# Actor_8_Channel.net
KiCad netlist of a schematic drawn in EAGLE
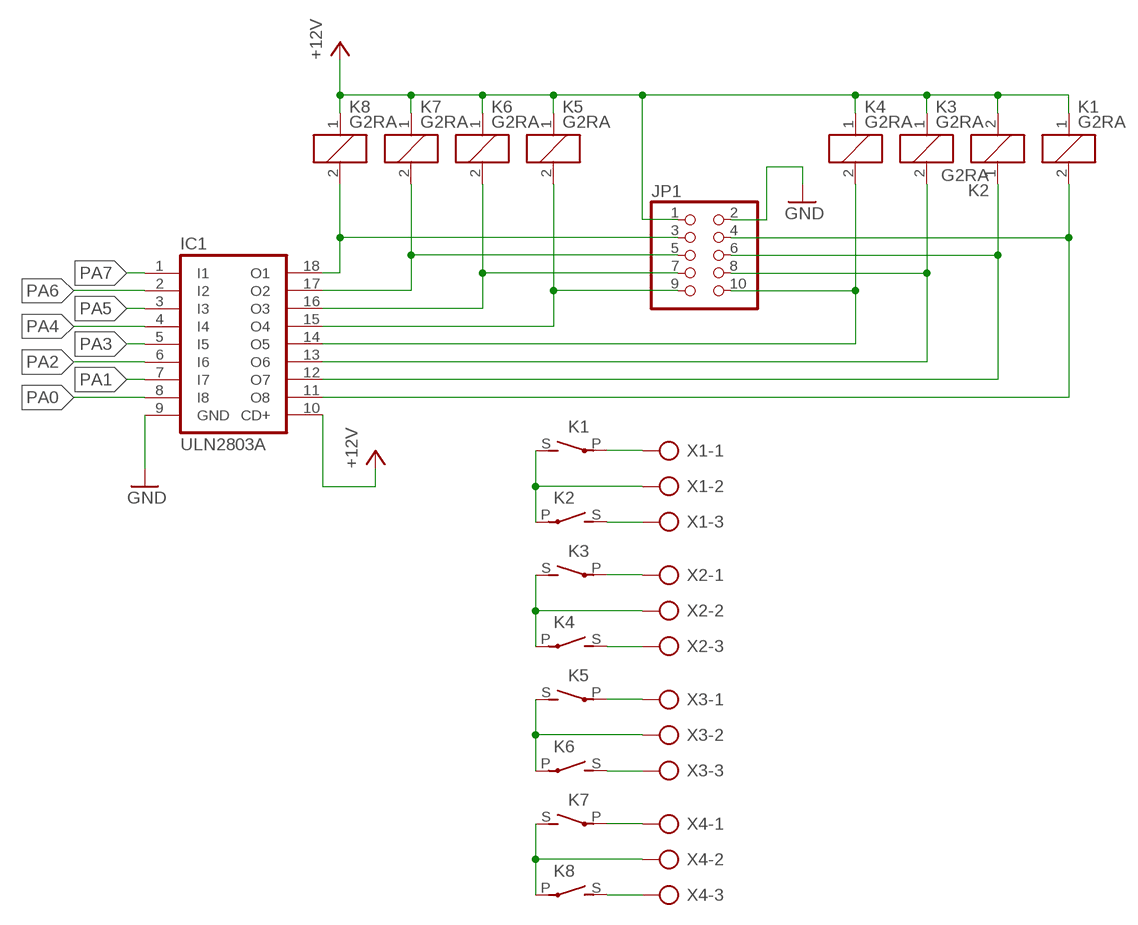
[diagram p0: schematic, sheet 1, part 1 of 2]
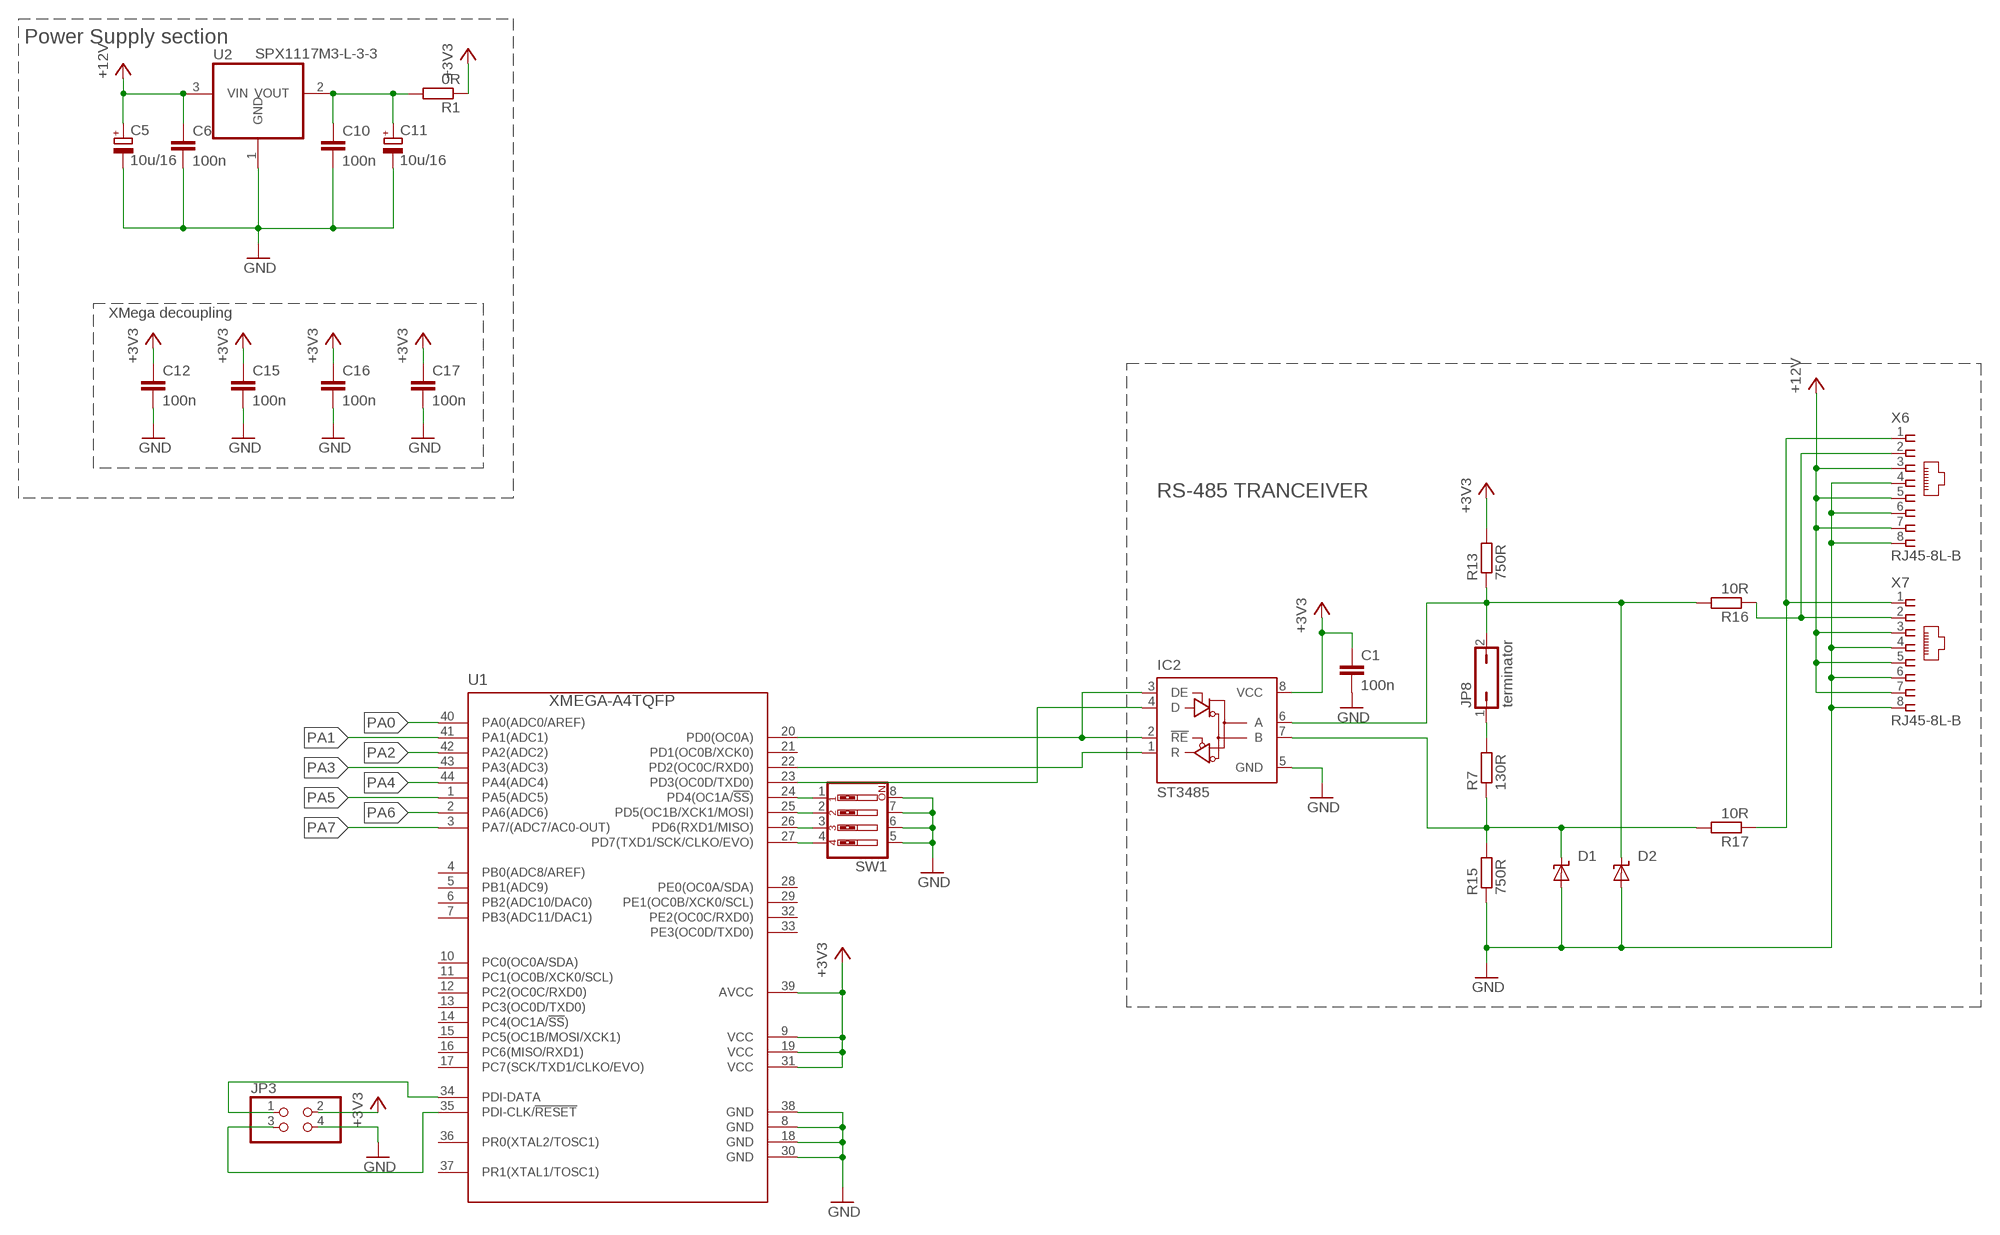
[diagram p1: schematic, sheet 1, part 2 of 2]

(export (version "E")
  (design (tool "Eeschema 10.0.6"))
  (components
    (comp (ref "C1")
      (value "100n")
      (footprint "eagle-import:C1206")
      (libsource (lib "eagle-import") (part "C-EUC1206"))
    )
    (comp (ref "C5")
      (value "10u/16")
      (footprint "eagle-import:SMC_C")
      (libsource (lib "eagle-import") (part "CPOL-EUSMCC"))
    )
    (comp (ref "C6")
      (value "100n")
      (footprint "eagle-import:C1206")
      (libsource (lib "eagle-import") (part "C-EUC1206"))
    )
    (comp (ref "C10")
      (value "100n")
      (footprint "eagle-import:C1206")
      (libsource (lib "eagle-import") (part "C-EUC1206"))
    )
    (comp (ref "C11")
      (value "10u/16")
      (footprint "eagle-import:SMC_C")
      (libsource (lib "eagle-import") (part "CPOL-EUSMCC"))
    )
    (comp (ref "C12")
      (value "100n")
      (footprint "eagle-import:C1206")
      (libsource (lib "eagle-import") (part "C-EUC1206"))
    )
    (comp (ref "C15")
      (value "100n")
      (footprint "eagle-import:C1206")
      (libsource (lib "eagle-import") (part "C-EUC1206"))
    )
    (comp (ref "C16")
      (value "100n")
      (footprint "eagle-import:C1206")
      (libsource (lib "eagle-import") (part "C-EUC1206"))
    )
    (comp (ref "C17")
      (value "100n")
      (footprint "eagle-import:C1206")
      (libsource (lib "eagle-import") (part "C-EUC1206"))
    )
    (comp (ref "D1")
      (value "SUPPRESSOR-SMBJ")
      (footprint "eagle-import:SMBJ")
      (libsource (lib "eagle-import") (part "SUPPRESSOR-SMBJ"))
    )
    (comp (ref "D2")
      (value "SUPPRESSOR-SMBJ")
      (footprint "eagle-import:SMBJ")
      (libsource (lib "eagle-import") (part "SUPPRESSOR-SMBJ"))
    )
    (comp (ref "IC1")
      (value "ULN2803A")
      (footprint "eagle-import:SO18W")
      (libsource (lib "eagle-import") (part "ULN2803ASMD_SO18"))
    )
    (comp (ref "IC2")
      (value "ST3485")
      (footprint "eagle-import:D_R-PDSO-G8")
      (libsource (lib "eagle-import") (part "75176AD"))
    )
    (comp (ref "JP1")
      (value "PINHD-2X5")
      (footprint "eagle-import:2X05")
      (libsource (lib "eagle-import") (part "PINHD-2X5"))
    )
    (comp (ref "JP3")
      (value "PINHD-2X2")
      (footprint "eagle-import:2X02")
      (libsource (lib "eagle-import") (part "PINHD-2X2"))
    )
    (comp (ref "JP8")
      (value "terminator")
      (footprint "eagle-import:JP1")
      (libsource (lib "eagle-import") (part "JP1Q"))
    )
    (comp (ref "K1")
      (value "G2RA")
      (footprint "eagle-import:G2RA")
      (libsource (lib "eagle-import") (part "G2RA"))
    )
    (comp (ref "K2")
      (value "G2RA")
      (footprint "eagle-import:G2RA")
      (libsource (lib "eagle-import") (part "G2RA"))
    )
    (comp (ref "K3")
      (value "G2RA")
      (footprint "eagle-import:G2RA")
      (libsource (lib "eagle-import") (part "G2RA"))
    )
    (comp (ref "K4")
      (value "G2RA")
      (footprint "eagle-import:G2RA")
      (libsource (lib "eagle-import") (part "G2RA"))
    )
    (comp (ref "K5")
      (value "G2RA")
      (footprint "eagle-import:G2RA")
      (libsource (lib "eagle-import") (part "G2RA"))
    )
    (comp (ref "K6")
      (value "G2RA")
      (footprint "eagle-import:G2RA")
      (libsource (lib "eagle-import") (part "G2RA"))
    )
    (comp (ref "K7")
      (value "G2RA")
      (footprint "eagle-import:G2RA")
      (libsource (lib "eagle-import") (part "G2RA"))
    )
    (comp (ref "K8")
      (value "G2RA")
      (footprint "eagle-import:G2RA")
      (libsource (lib "eagle-import") (part "G2RA"))
    )
    (comp (ref "R1")
      (value "0R")
      (footprint "eagle-import:M1206")
      (libsource (lib "eagle-import") (part "R-EU_M1206"))
    )
    (comp (ref "R7")
      (value "130R")
      (footprint "eagle-import:M1206")
      (libsource (lib "eagle-import") (part "R-EU_M1206"))
    )
    (comp (ref "R13")
      (value "750R")
      (footprint "eagle-import:M1206")
      (libsource (lib "eagle-import") (part "R-EU_M1206"))
    )
    (comp (ref "R15")
      (value "750R")
      (footprint "eagle-import:M1206")
      (libsource (lib "eagle-import") (part "R-EU_M1206"))
    )
    (comp (ref "R16")
      (value "10R")
      (footprint "eagle-import:M1206")
      (libsource (lib "eagle-import") (part "R-EU_M1206"))
    )
    (comp (ref "R17")
      (value "10R")
      (footprint "eagle-import:M1206")
      (libsource (lib "eagle-import") (part "R-EU_M1206"))
    )
    (comp (ref "SW1")
      (value "SW_DIP-4")
      (footprint "eagle-import:EDG-04")
      (libsource (lib "eagle-import") (part "SW_DIP-4"))
    )
    (comp (ref "U1")
      (value "XMEGA-A4TQFP")
      (footprint "eagle-import:TQFP44")
      (libsource (lib "eagle-import") (part "XMEGA-A4TQFP"))
    )
    (comp (ref "U2")
      (value "SPX1117M3-L-3-3")
      (footprint "eagle-import:SOT223")
      (fields (field (name "MPN") "REG1117"))
      (libsource (lib "eagle-import") (part "REG1117"))
    )
    (comp (ref "X1")
      (value "MKDS_5/3-7,5")
      (footprint "eagle-import:MKDS_5_-750")
      (libsource (lib "eagle-import") (part "MKDS_5/3-7,5"))
    )
    (comp (ref "X2")
      (value "MKDS_5/3-7,5")
      (footprint "eagle-import:MKDS_5_-750")
      (libsource (lib "eagle-import") (part "MKDS_5/3-7,5"))
    )
    (comp (ref "X3")
      (value "MKDS_5/3-7,5")
      (footprint "eagle-import:MKDS_5_-750")
      (libsource (lib "eagle-import") (part "MKDS_5/3-7,5"))
    )
    (comp (ref "X4")
      (value "MKDS_5/3-7,5")
      (footprint "eagle-import:MKDS_5_-750")
      (libsource (lib "eagle-import") (part "MKDS_5/3-7,5"))
    )
    (comp (ref "X6")
      (value "RJ45-8L-B")
      (footprint "eagle-import:RJ45-NO-SHIELD")
      (fields (field (name "MF") "TYCO ELECTRONICS"))
      (libsource (lib "eagle-import") (part "RJ45-8L-B"))
    )
    (comp (ref "X7")
      (value "RJ45-8L-B")
      (footprint "eagle-import:RJ45-NO-SHIELD")
      (fields (field (name "MF") "TYCO ELECTRONICS"))
      (libsource (lib "eagle-import") (part "RJ45-8L-B"))
    )
  )
  (nets
    (net (code "1") (name "+3V3") (class "Default")
      (node (ref "C1") (pin "1") (pinfunction "1_1") (pintype "passive"))
      (node (ref "C10") (pin "1") (pinfunction "1_1") (pintype "passive"))
      (node (ref "C11") (pin "+") (pinfunction "+_+") (pintype "passive"))
      (node (ref "C12") (pin "1") (pinfunction "1_1") (pintype "passive"))
      (node (ref "C15") (pin "1") (pinfunction "1_1") (pintype "passive"))
      (node (ref "C16") (pin "1") (pinfunction "1_1") (pintype "passive"))
      (node (ref "C17") (pin "1") (pinfunction "1_1") (pintype "passive"))
      (node (ref "IC2") (pin "8") (pinfunction "VCC_8") (pintype "power_in"))
      (node (ref "JP3") (pin "2") (pinfunction "2_2") (pintype "passive"))
      (node (ref "R1") (pin "1") (pinfunction "1_1") (pintype "passive"))
      (node (ref "R1") (pin "2") (pinfunction "2_2") (pintype "passive"))
      (node (ref "R13") (pin "2") (pinfunction "2_2") (pintype "passive"))
      (node (ref "U1") (pin "19") (pinfunction "VCC_19") (pintype "power_in"))
      (node (ref "U1") (pin "31") (pinfunction "VCC_31") (pintype "power_in"))
      (node (ref "U1") (pin "39") (pinfunction "AVCC_39") (pintype "power_in"))
      (node (ref "U1") (pin "9") (pinfunction "VCC_9") (pintype "power_in"))
      (node (ref "U2") (pin "2") (pinfunction "VOUT_2") (pintype "output"))
    )
    (net (code "2") (name "+12V") (class "Default")
      (node (ref "C5") (pin "+") (pinfunction "+_+") (pintype "passive"))
      (node (ref "C6") (pin "1") (pinfunction "1_1") (pintype "passive"))
      (node (ref "IC1") (pin "10") (pinfunction "CD+_10") (pintype "passive"))
      (node (ref "JP1") (pin "1") (pinfunction "1_1") (pintype "passive"))
      (node (ref "K1") (pin "1") (pinfunction "1_1") (pintype "passive"))
      (node (ref "K2") (pin "2") (pinfunction "2_2") (pintype "passive"))
      (node (ref "K3") (pin "1") (pinfunction "1_1") (pintype "passive"))
      (node (ref "K4") (pin "1") (pinfunction "1_1") (pintype "passive"))
      (node (ref "K5") (pin "1") (pinfunction "1_1") (pintype "passive"))
      (node (ref "K6") (pin "1") (pinfunction "1_1") (pintype "passive"))
      (node (ref "K7") (pin "1") (pinfunction "1_1") (pintype "passive"))
      (node (ref "K8") (pin "1") (pinfunction "1_1") (pintype "passive"))
      (node (ref "U2") (pin "3") (pinfunction "VIN_3") (pintype "input"))
      (node (ref "X6") (pin "3") (pinfunction "3_3") (pintype "passive"))
      (node (ref "X6") (pin "5") (pinfunction "5_5") (pintype "passive"))
      (node (ref "X6") (pin "7") (pinfunction "7_7") (pintype "passive"))
      (node (ref "X7") (pin "3") (pinfunction "3_3") (pintype "passive"))
      (node (ref "X7") (pin "5") (pinfunction "5_5") (pintype "passive"))
      (node (ref "X7") (pin "7") (pinfunction "7_7") (pintype "passive"))
    )
    (net (code "3") (name "GND") (class "Default")
      (node (ref "C1") (pin "2") (pinfunction "2_2") (pintype "passive"))
      (node (ref "C10") (pin "2") (pinfunction "2_2") (pintype "passive"))
      (node (ref "C11") (pin "-") (pinfunction "-_-") (pintype "passive"))
      (node (ref "C12") (pin "2") (pinfunction "2_2") (pintype "passive"))
      (node (ref "C15") (pin "2") (pinfunction "2_2") (pintype "passive"))
      (node (ref "C16") (pin "2") (pinfunction "2_2") (pintype "passive"))
      (node (ref "C17") (pin "2") (pinfunction "2_2") (pintype "passive"))
      (node (ref "C5") (pin "-") (pinfunction "-_-") (pintype "passive"))
      (node (ref "C6") (pin "2") (pinfunction "2_2") (pintype "passive"))
      (node (ref "D1") (pin "A") (pinfunction "A_A") (pintype "passive"))
      (node (ref "D2") (pin "A") (pinfunction "A_A") (pintype "passive"))
      (node (ref "IC1") (pin "9") (pinfunction "GND_9") (pintype "power_in"))
      (node (ref "IC2") (pin "5") (pinfunction "GND_5") (pintype "power_in"))
      (node (ref "JP1") (pin "2") (pinfunction "2_2") (pintype "passive"))
      (node (ref "JP3") (pin "4") (pinfunction "4_4") (pintype "passive"))
      (node (ref "R15") (pin "1") (pinfunction "1_1") (pintype "passive"))
      (node (ref "SW1") (pin "5") (pinfunction "5_5") (pintype "passive"))
      (node (ref "SW1") (pin "6") (pinfunction "6_6") (pintype "passive"))
      (node (ref "SW1") (pin "7") (pinfunction "7_7") (pintype "passive"))
      (node (ref "SW1") (pin "8") (pinfunction "8_8") (pintype "passive"))
      (node (ref "U1") (pin "18") (pinfunction "GND_18") (pintype "power_in"))
      (node (ref "U1") (pin "30") (pinfunction "GND_30") (pintype "power_in"))
      (node (ref "U1") (pin "38") (pinfunction "GND_38") (pintype "power_in"))
      (node (ref "U1") (pin "8") (pinfunction "GND_8") (pintype "power_in"))
      (node (ref "U2") (pin "1") (pinfunction "GND_1") (pintype "power_in"))
      (node (ref "X6") (pin "4") (pinfunction "4_4") (pintype "passive"))
      (node (ref "X6") (pin "6") (pinfunction "6_6") (pintype "passive"))
      (node (ref "X6") (pin "8") (pinfunction "8_8") (pintype "passive"))
      (node (ref "X7") (pin "4") (pinfunction "4_4") (pintype "passive"))
      (node (ref "X7") (pin "6") (pinfunction "6_6") (pintype "passive"))
      (node (ref "X7") (pin "8") (pinfunction "8_8") (pintype "passive"))
    )
    (net (code "4") (name "Net-(IC1-O1)") (class "Default")
      (node (ref "IC1") (pin "18") (pinfunction "O1_18") (pintype "open_collector"))
      (node (ref "JP1") (pin "3") (pinfunction "3_3") (pintype "passive"))
      (node (ref "K8") (pin "2") (pinfunction "2_2") (pintype "passive"))
    )
    (net (code "5") (name "Net-(IC1-O2)") (class "Default")
      (node (ref "IC1") (pin "17") (pinfunction "O2_17") (pintype "open_collector"))
      (node (ref "JP1") (pin "5") (pinfunction "5_5") (pintype "passive"))
      (node (ref "K7") (pin "2") (pinfunction "2_2") (pintype "passive"))
    )
    (net (code "6") (name "Net-(IC1-O3)") (class "Default")
      (node (ref "IC1") (pin "16") (pinfunction "O3_16") (pintype "open_collector"))
      (node (ref "JP1") (pin "7") (pinfunction "7_7") (pintype "passive"))
      (node (ref "K6") (pin "2") (pinfunction "2_2") (pintype "passive"))
    )
    (net (code "7") (name "Net-(IC1-O4)") (class "Default")
      (node (ref "IC1") (pin "15") (pinfunction "O4_15") (pintype "open_collector"))
      (node (ref "JP1") (pin "9") (pinfunction "9_9") (pintype "passive"))
      (node (ref "K5") (pin "2") (pinfunction "2_2") (pintype "passive"))
    )
    (net (code "8") (name "Net-(IC1-O5)") (class "Default")
      (node (ref "IC1") (pin "14") (pinfunction "O5_14") (pintype "open_collector"))
      (node (ref "JP1") (pin "10") (pinfunction "10_10") (pintype "passive"))
      (node (ref "K4") (pin "2") (pinfunction "2_2") (pintype "passive"))
    )
    (net (code "9") (name "Net-(IC1-O6)") (class "Default")
      (node (ref "IC1") (pin "13") (pinfunction "O6_13") (pintype "open_collector"))
      (node (ref "JP1") (pin "8") (pinfunction "8_8") (pintype "passive"))
      (node (ref "K3") (pin "2") (pinfunction "2_2") (pintype "passive"))
    )
    (net (code "10") (name "Net-(IC1-O7)") (class "Default")
      (node (ref "IC1") (pin "12") (pinfunction "O7_12") (pintype "open_collector"))
      (node (ref "JP1") (pin "6") (pinfunction "6_6") (pintype "passive"))
      (node (ref "K2") (pin "1") (pinfunction "1_1") (pintype "passive"))
    )
    (net (code "11") (name "Net-(IC1-O8)") (class "Default")
      (node (ref "IC1") (pin "11") (pinfunction "O8_11") (pintype "open_collector"))
      (node (ref "JP1") (pin "4") (pinfunction "4_4") (pintype "passive"))
      (node (ref "K1") (pin "2") (pinfunction "2_2") (pintype "passive"))
    )
    (net (code "12") (name "Net-(IC2-A)") (class "Default")
      (node (ref "D2") (pin "C") (pinfunction "C_C") (pintype "passive"))
      (node (ref "IC2") (pin "6") (pinfunction "A_6") (pintype "output"))
      (node (ref "JP8") (pin "2") (pinfunction "2_2") (pintype "passive"))
      (node (ref "R13") (pin "1") (pinfunction "1_1") (pintype "passive"))
      (node (ref "R16") (pin "2") (pinfunction "2_2") (pintype "passive"))
    )
    (net (code "13") (name "Net-(IC2-B)") (class "Default")
      (node (ref "D1") (pin "C") (pinfunction "C_C") (pintype "passive"))
      (node (ref "IC2") (pin "7") (pinfunction "B_7") (pintype "output"))
      (node (ref "R15") (pin "2") (pinfunction "2_2") (pintype "passive"))
      (node (ref "R17") (pin "2") (pinfunction "2_2") (pintype "passive"))
      (node (ref "R7") (pin "1") (pinfunction "1_1") (pintype "passive"))
    )
    (net (code "14") (name "Net-(IC2-D)") (class "Default")
      (node (ref "IC2") (pin "4") (pinfunction "D_4") (pintype "input"))
      (node (ref "U1") (pin "23") (pinfunction "PD3(OC0D/TXD0)_23") (pintype "bidirectional"))
    )
    (net (code "15") (name "Net-(IC2-DE)") (class "Default")
      (node (ref "IC2") (pin "2") (pinfunction "~{RE}_2") (pintype "input"))
      (node (ref "IC2") (pin "3") (pinfunction "DE_3") (pintype "input"))
      (node (ref "U1") (pin "20") (pinfunction "PD0(OC0A)_20") (pintype "bidirectional"))
    )
    (net (code "16") (name "Net-(IC2-R)") (class "Default")
      (node (ref "IC2") (pin "1") (pinfunction "R_1") (pintype "input"))
      (node (ref "U1") (pin "22") (pinfunction "PD2(OC0C/RXD0)_22") (pintype "bidirectional"))
    )
    (net (code "17") (name "Net-(JP8-Pad1)") (class "Default")
      (node (ref "JP8") (pin "1") (pinfunction "1_1") (pintype "passive"))
      (node (ref "R7") (pin "2") (pinfunction "2_2") (pintype "passive"))
    )
    (net (code "18") (name "Net-(R16-Pad1)") (class "Default")
      (node (ref "R16") (pin "1") (pinfunction "1_1") (pintype "passive"))
      (node (ref "X6") (pin "2") (pinfunction "2_2") (pintype "passive"))
      (node (ref "X7") (pin "2") (pinfunction "2_2") (pintype "passive"))
    )
    (net (code "19") (name "Net-(R17-Pad1)") (class "Default")
      (node (ref "R17") (pin "1") (pinfunction "1_1") (pintype "passive"))
      (node (ref "X6") (pin "1") (pinfunction "1_1") (pintype "passive"))
      (node (ref "X7") (pin "1") (pinfunction "1_1") (pintype "passive"))
    )
    (net (code "20") (name "Net-(U1-PD4(OC1A{slash}~{SS}))") (class "Default")
      (node (ref "SW1") (pin "1") (pinfunction "1_1") (pintype "passive"))
      (node (ref "U1") (pin "24") (pinfunction "PD4(OC1A/~{SS})_24") (pintype "bidirectional"))
    )
    (net (code "21") (name "Net-(U1-PD5(OC1B{slash}XCK1{slash}MOSI))") (class "Default")
      (node (ref "SW1") (pin "2") (pinfunction "2_2") (pintype "passive"))
      (node (ref "U1") (pin "25") (pinfunction "PD5(OC1B/XCK1/MOSI)_25") (pintype "bidirectional"))
    )
    (net (code "22") (name "Net-(U1-PD6(RXD1{slash}MISO))") (class "Default")
      (node (ref "SW1") (pin "3") (pinfunction "3_3") (pintype "passive"))
      (node (ref "U1") (pin "26") (pinfunction "PD6(RXD1/MISO)_26") (pintype "bidirectional"))
    )
    (net (code "23") (name "Net-(U1-PD7(TXD1{slash}SCK{slash}CLKO{slash}EVO))") (class "Default")
      (node (ref "SW1") (pin "4") (pinfunction "4_4") (pintype "passive"))
      (node (ref "U1") (pin "27") (pinfunction "PD7(TXD1/SCK/CLKO/EVO)_27") (pintype "bidirectional"))
    )
    (net (code "24") (name "Net-(U1-PDI-CLK{slash}~{RESET})") (class "Default")
      (node (ref "JP3") (pin "3") (pinfunction "3_3") (pintype "passive"))
      (node (ref "U1") (pin "35") (pinfunction "PDI-CLK/~{RESET}_35") (pintype "input"))
    )
    (net (code "25") (name "Net-(U1-PDI-DATA)") (class "Default")
      (node (ref "JP3") (pin "1") (pinfunction "1_1") (pintype "passive"))
      (node (ref "U1") (pin "34") (pinfunction "PDI-DATA_34") (pintype "bidirectional"))
    )
    (net (code "26") (name "Net-(X1A-KL)") (class "Default")
      (node (ref "K1") (pin "P") (pinfunction "P_P") (pintype "passive"))
      (node (ref "X1") (pin "1") (pinfunction "KL_1") (pintype "passive"))
    )
    (net (code "27") (name "Net-(X1B-KL)") (class "Default")
      (node (ref "K1") (pin "S") (pinfunction "S_S") (pintype "passive"))
      (node (ref "K2") (pin "P") (pinfunction "P_P") (pintype "passive"))
      (node (ref "X1") (pin "2") (pinfunction "KL_2") (pintype "passive"))
    )
    (net (code "28") (name "Net-(X1C-KL)") (class "Default")
      (node (ref "K2") (pin "S") (pinfunction "S_S") (pintype "passive"))
      (node (ref "X1") (pin "3") (pinfunction "KL_3") (pintype "passive"))
    )
    (net (code "29") (name "Net-(X2A-KL)") (class "Default")
      (node (ref "K3") (pin "P") (pinfunction "P_P") (pintype "passive"))
      (node (ref "X2") (pin "1") (pinfunction "KL_1") (pintype "passive"))
    )
    (net (code "30") (name "Net-(X2B-KL)") (class "Default")
      (node (ref "K3") (pin "S") (pinfunction "S_S") (pintype "passive"))
      (node (ref "K4") (pin "P") (pinfunction "P_P") (pintype "passive"))
      (node (ref "X2") (pin "2") (pinfunction "KL_2") (pintype "passive"))
    )
    (net (code "31") (name "Net-(X2C-KL)") (class "Default")
      (node (ref "K4") (pin "S") (pinfunction "S_S") (pintype "passive"))
      (node (ref "X2") (pin "3") (pinfunction "KL_3") (pintype "passive"))
    )
    (net (code "32") (name "Net-(X3A-KL)") (class "Default")
      (node (ref "K5") (pin "P") (pinfunction "P_P") (pintype "passive"))
      (node (ref "X3") (pin "1") (pinfunction "KL_1") (pintype "passive"))
    )
    (net (code "33") (name "Net-(X3B-KL)") (class "Default")
      (node (ref "K5") (pin "S") (pinfunction "S_S") (pintype "passive"))
      (node (ref "K6") (pin "P") (pinfunction "P_P") (pintype "passive"))
      (node (ref "X3") (pin "2") (pinfunction "KL_2") (pintype "passive"))
    )
    (net (code "34") (name "Net-(X3C-KL)") (class "Default")
      (node (ref "K6") (pin "S") (pinfunction "S_S") (pintype "passive"))
      (node (ref "X3") (pin "3") (pinfunction "KL_3") (pintype "passive"))
    )
    (net (code "35") (name "Net-(X4A-KL)") (class "Default")
      (node (ref "K7") (pin "P") (pinfunction "P_P") (pintype "passive"))
      (node (ref "X4") (pin "1") (pinfunction "KL_1") (pintype "passive"))
    )
    (net (code "36") (name "Net-(X4B-KL)") (class "Default")
      (node (ref "K7") (pin "S") (pinfunction "S_S") (pintype "passive"))
      (node (ref "K8") (pin "P") (pinfunction "P_P") (pintype "passive"))
      (node (ref "X4") (pin "2") (pinfunction "KL_2") (pintype "passive"))
    )
    (net (code "37") (name "Net-(X4C-KL)") (class "Default")
      (node (ref "K8") (pin "S") (pinfunction "S_S") (pintype "passive"))
      (node (ref "X4") (pin "3") (pinfunction "KL_3") (pintype "passive"))
    )
    (net (code "38") (name "PA0") (class "Default")
      (node (ref "IC1") (pin "8") (pinfunction "I8_8") (pintype "input"))
      (node (ref "U1") (pin "40") (pinfunction "PA0(ADC0/AREF)_40") (pintype "bidirectional"))
    )
    (net (code "39") (name "PA1") (class "Default")
      (node (ref "IC1") (pin "7") (pinfunction "I7_7") (pintype "input"))
      (node (ref "U1") (pin "41") (pinfunction "PA1(ADC1)_41") (pintype "bidirectional"))
    )
    (net (code "40") (name "PA2") (class "Default")
      (node (ref "IC1") (pin "6") (pinfunction "I6_6") (pintype "input"))
      (node (ref "U1") (pin "42") (pinfunction "PA2(ADC2)_42") (pintype "bidirectional"))
    )
    (net (code "41") (name "PA3") (class "Default")
      (node (ref "IC1") (pin "5") (pinfunction "I5_5") (pintype "input"))
      (node (ref "U1") (pin "43") (pinfunction "PA3(ADC3)_43") (pintype "bidirectional"))
    )
    (net (code "42") (name "PA4") (class "Default")
      (node (ref "IC1") (pin "4") (pinfunction "I4_4") (pintype "input"))
      (node (ref "U1") (pin "44") (pinfunction "PA4(ADC4)_44") (pintype "bidirectional"))
    )
    (net (code "43") (name "PA5") (class "Default")
      (node (ref "IC1") (pin "3") (pinfunction "I3_3") (pintype "input"))
      (node (ref "U1") (pin "1") (pinfunction "PA5(ADC5)_1") (pintype "bidirectional"))
    )
    (net (code "44") (name "PA6") (class "Default")
      (node (ref "IC1") (pin "2") (pinfunction "I2_2") (pintype "input"))
      (node (ref "U1") (pin "2") (pinfunction "PA6(ADC6)_2") (pintype "bidirectional"))
    )
    (net (code "45") (name "PA7") (class "Default")
      (node (ref "IC1") (pin "1") (pinfunction "I1_1") (pintype "input"))
      (node (ref "U1") (pin "3") (pinfunction "PA7/(ADC7/AC0-OUT)_3") (pintype "bidirectional"))
    )
    (net (code "46") (name "unconnected-(U1-PB0(ADC8{slash}AREF)-Pad4)") (class "Default")
      (node (ref "U1") (pin "4") (pinfunction "PB0(ADC8/AREF)_4") (pintype "bidirectional"))
    )
    (net (code "47") (name "unconnected-(U1-PB1(ADC9)-Pad5)") (class "Default")
      (node (ref "U1") (pin "5") (pinfunction "PB1(ADC9)_5") (pintype "bidirectional"))
    )
    (net (code "48") (name "unconnected-(U1-PB2(ADC10{slash}DAC0)-Pad6)") (class "Default")
      (node (ref "U1") (pin "6") (pinfunction "PB2(ADC10/DAC0)_6") (pintype "bidirectional"))
    )
    (net (code "49") (name "unconnected-(U1-PB3(ADC11{slash}DAC1)-Pad7)") (class "Default")
      (node (ref "U1") (pin "7") (pinfunction "PB3(ADC11/DAC1)_7") (pintype "bidirectional"))
    )
    (net (code "50") (name "unconnected-(U1-PC0(OC0A{slash}SDA)-Pad10)") (class "Default")
      (node (ref "U1") (pin "10") (pinfunction "PC0(OC0A/SDA)_10") (pintype "bidirectional"))
    )
    (net (code "51") (name "unconnected-(U1-PC1(OC0B{slash}XCK0{slash}SCL)-Pad11)") (class "Default")
      (node (ref "U1") (pin "11") (pinfunction "PC1(OC0B/XCK0/SCL)_11") (pintype "bidirectional"))
    )
    (net (code "52") (name "unconnected-(U1-PC2(OC0C{slash}RXD0)-Pad12)") (class "Default")
      (node (ref "U1") (pin "12") (pinfunction "PC2(OC0C/RXD0)_12") (pintype "bidirectional"))
    )
    (net (code "53") (name "unconnected-(U1-PC3(OC0D{slash}TXD0)-Pad13)") (class "Default")
      (node (ref "U1") (pin "13") (pinfunction "PC3(OC0D/TXD0)_13") (pintype "bidirectional"))
    )
    (net (code "54") (name "unconnected-(U1-PC4(OC1A{slash}~{SS})-Pad14)") (class "Default")
      (node (ref "U1") (pin "14") (pinfunction "PC4(OC1A/~{SS})_14") (pintype "bidirectional"))
    )
    (net (code "55") (name "unconnected-(U1-PC5(OC1B{slash}MOSI{slash}XCK1)-Pad15)") (class "Default")
      (node (ref "U1") (pin "15") (pinfunction "PC5(OC1B/MOSI/XCK1)_15") (pintype "bidirectional"))
    )
    (net (code "56") (name "unconnected-(U1-PC6(MISO{slash}RXD1)-Pad16)") (class "Default")
      (node (ref "U1") (pin "16") (pinfunction "PC6(MISO/RXD1)_16") (pintype "bidirectional"))
    )
    (net (code "57") (name "unconnected-(U1-PC7(SCK{slash}TXD1{slash}CLKO{slash}EVO)-Pad17)") (class "Default")
      (node (ref "U1") (pin "17") (pinfunction "PC7(SCK/TXD1/CLKO/EVO)_17") (pintype "bidirectional"))
    )
    (net (code "58") (name "unconnected-(U1-PD1(OC0B{slash}XCK0)-Pad21)") (class "Default")
      (node (ref "U1") (pin "21") (pinfunction "PD1(OC0B/XCK0)_21") (pintype "bidirectional"))
    )
    (net (code "59") (name "unconnected-(U1-PE0(OC0A{slash}SDA)-Pad28)") (class "Default")
      (node (ref "U1") (pin "28") (pinfunction "PE0(OC0A/SDA)_28") (pintype "bidirectional"))
    )
    (net (code "60") (name "unconnected-(U1-PE1(OC0B{slash}XCK0{slash}SCL)-Pad29)") (class "Default")
      (node (ref "U1") (pin "29") (pinfunction "PE1(OC0B/XCK0/SCL)_29") (pintype "bidirectional"))
    )
    (net (code "61") (name "unconnected-(U1-PE2(OC0C{slash}RXD0)-Pad32)") (class "Default")
      (node (ref "U1") (pin "32") (pinfunction "PE2(OC0C/RXD0)_32") (pintype "bidirectional"))
    )
    (net (code "62") (name "unconnected-(U1-PE3(OC0D{slash}TXD0)-Pad33)") (class "Default")
      (node (ref "U1") (pin "33") (pinfunction "PE3(OC0D/TXD0)_33") (pintype "bidirectional"))
    )
    (net (code "63") (name "unconnected-(U1-PR0(XTAL2{slash}TOSC1)-Pad36)") (class "Default")
      (node (ref "U1") (pin "36") (pinfunction "PR0(XTAL2/TOSC1)_36") (pintype "bidirectional"))
    )
    (net (code "64") (name "unconnected-(U1-PR1(XTAL1{slash}TOSC1)-Pad37)") (class "Default")
      (node (ref "U1") (pin "37") (pinfunction "PR1(XTAL1/TOSC1)_37") (pintype "bidirectional"))
    )
  )
)
